# PowerSupply.net
KiCad netlist of a schematic drawn in Altium Designer
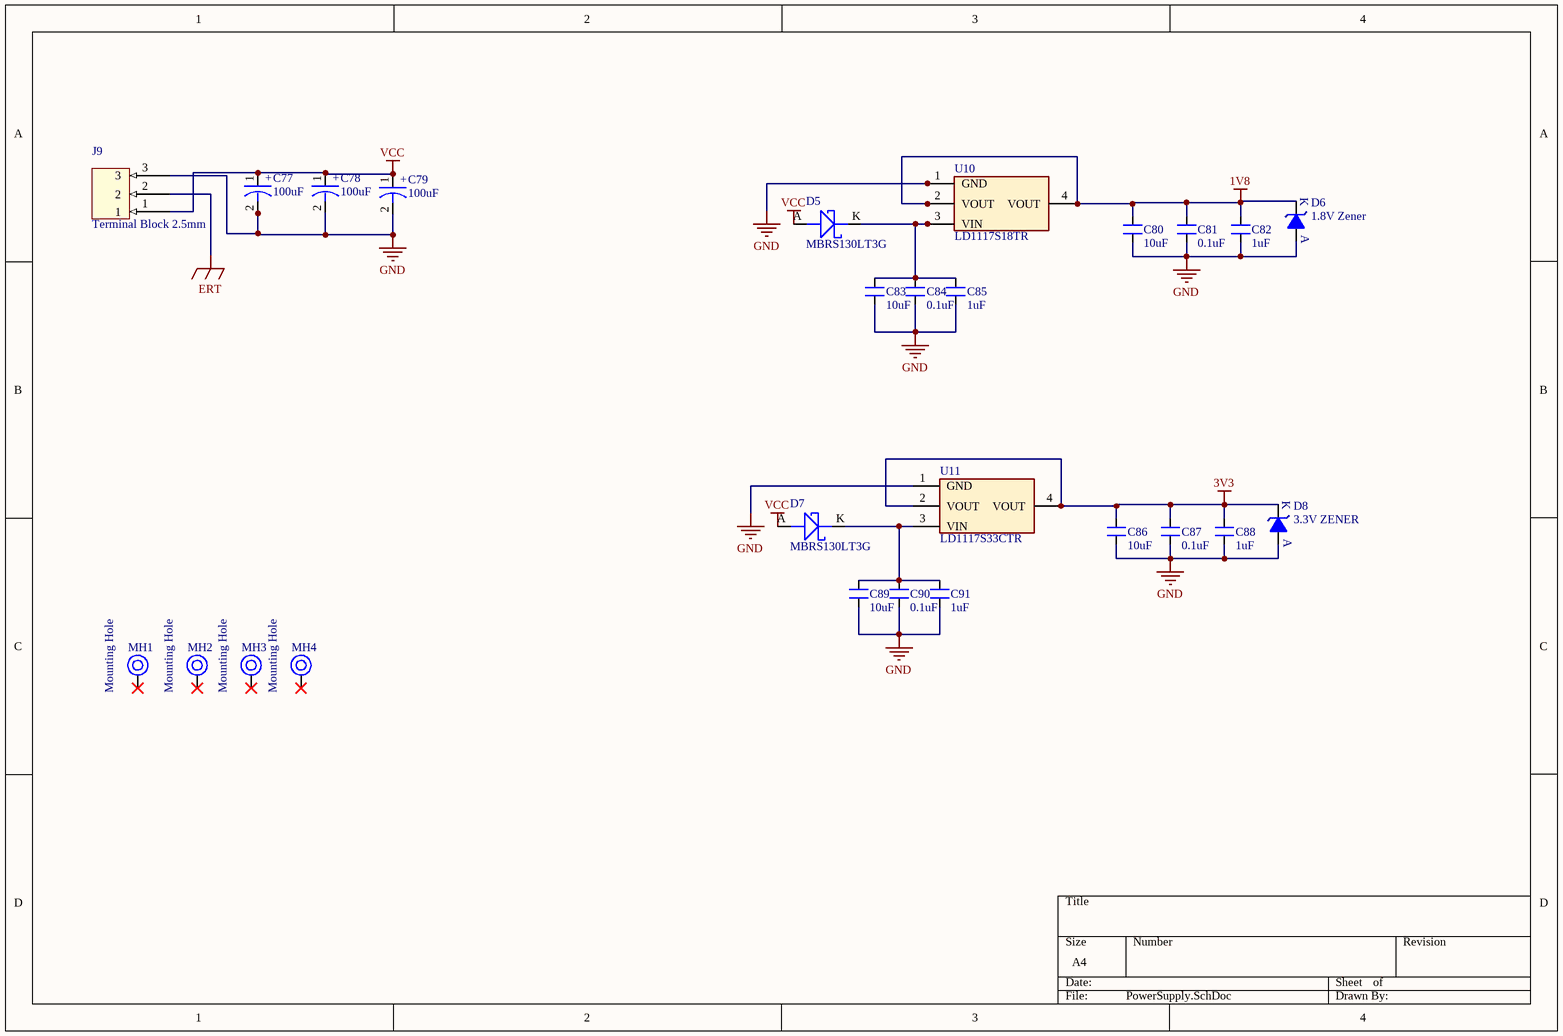
[diagram p0: PowerSupply.SchDoc]

(export (version "E")
  (design (tool "Eeschema 10.0.6"))
  (components
    (comp (ref "C77")
      (value "100uF")
      (footprint "ACAP_P236_D305_H303_RAD")
      (description "100µF 25V Aluminum Electrolytic Capacitors Radial, Can - SMD 1000 Hrs @ 105°C")
      (fields
        (field (name "MANUFACTURER") "Nichicon")
        (field (name "MANUFACTURER PART NUMBER") "UWT1E101MCL1GS")
      )
      (libsource (lib "ESTEEMPCBLIB") (part "CAP-P_100uF-25V-20%-RAD"))
    )
    (comp (ref "C78")
      (value "100uF")
      (footprint "ACAP_P236_D305_H303_RAD")
      (description "100µF 25V Aluminum Electrolytic Capacitors Radial, Can - SMD 1000 Hrs @ 105°C")
      (fields
        (field (name "MANUFACTURER") "Nichicon")
        (field (name "MANUFACTURER PART NUMBER") "UWT1E101MCL1GS")
      )
      (libsource (lib "ESTEEMPCBLIB") (part "CAP-P_100uF-25V-20%-RAD"))
    )
    (comp (ref "C79")
      (value "100uF")
      (footprint "ACAP_P236_D305_H303_RAD")
      (description "100µF 25V Aluminum Electrolytic Capacitors Radial, Can - SMD 1000 Hrs @ 105°C")
      (fields
        (field (name "MANUFACTURER") "Nichicon")
        (field (name "MANUFACTURER PART NUMBER") "UWT1E101MCL1GS")
      )
      (libsource (lib "ESTEEMPCBLIB") (part "CAP-P_100uF-25V-20%-RAD"))
    )
    (comp (ref "C80")
      (value "10uF")
      (footprint "CAP_1206")
      (description "10µF ±10% 50V Ceramic Capacitor X7R 1206 (3216 Metric)")
      (fields
        (field (name "MANUFACTURER") "KEMET")
        (field (name "MANUFACTURER PART NUMBER") "CL31B106KBHNNNE")
      )
      (libsource (lib "ESTEEMPCBLIB") (part "CAP_10uF-50V-10%-1206"))
    )
    (comp (ref "C81")
      (value "0.1uF")
      (footprint "CAP_0805")
      (description "0.1µF ±10% 50V Ceramic Capacitor X7R 0805 (2012 Metric)")
      (fields
        (field (name "MANUFACTURER") "Samsung")
        (field (name "MANUFACTURER PART NUMBER") "CL21B104KBCNNNC")
      )
      (libsource (lib "ESTEEMPCBLIB") (part "CAP_0.1uF-50V-10%-0805"))
    )
    (comp (ref "C82")
      (value "1uF")
      (footprint "CAP_0805")
      (description "1µF ±5% 50V Ceramic Capacitor X7R 0805 (2012 Metric)")
      (fields
        (field (name "MANUFACTURER") "Samsung")
        (field (name "MANUFACTURER PART NUMBER") "CC0805JKX7R9BB105")
      )
      (libsource (lib "ESTEEMPCBLIB") (part "CAP_1uF-50V-5%-0805"))
    )
    (comp (ref "C83")
      (value "10uF")
      (footprint "CAP_1206")
      (description "10µF ±10% 50V Ceramic Capacitor X7R 1206 (3216 Metric)")
      (fields
        (field (name "MANUFACTURER") "KEMET")
        (field (name "MANUFACTURER PART NUMBER") "CL31B106KBHNNNE")
      )
      (libsource (lib "ESTEEMPCBLIB") (part "CAP_10uF-50V-10%-1206"))
    )
    (comp (ref "C84")
      (value "0.1uF")
      (footprint "CAP_0805")
      (description "0.1µF ±10% 50V Ceramic Capacitor X7R 0805 (2012 Metric)")
      (fields
        (field (name "MANUFACTURER") "Samsung")
        (field (name "MANUFACTURER PART NUMBER") "CL21B104KBCNNNC")
      )
      (libsource (lib "ESTEEMPCBLIB") (part "CAP_0.1uF-50V-10%-0805"))
    )
    (comp (ref "C85")
      (value "1uF")
      (footprint "CAP_0805")
      (description "1µF ±5% 50V Ceramic Capacitor X7R 0805 (2012 Metric)")
      (fields
        (field (name "MANUFACTURER") "Samsung")
        (field (name "MANUFACTURER PART NUMBER") "CC0805JKX7R9BB105")
      )
      (libsource (lib "ESTEEMPCBLIB") (part "CAP_1uF-50V-5%-0805"))
    )
    (comp (ref "C86")
      (value "10uF")
      (footprint "CAP_1206")
      (description "10µF ±10% 50V Ceramic Capacitor X7R 1206 (3216 Metric)")
      (fields
        (field (name "MANUFACTURER") "KEMET")
        (field (name "MANUFACTURER PART NUMBER") "CL31B106KBHNNNE")
      )
      (libsource (lib "ESTEEMPCBLIB") (part "CAP_10uF-50V-10%-1206"))
    )
    (comp (ref "C87")
      (value "0.1uF")
      (footprint "CAP_0805")
      (description "0.1µF ±10% 50V Ceramic Capacitor X7R 0805 (2012 Metric)")
      (fields
        (field (name "MANUFACTURER") "Samsung")
        (field (name "MANUFACTURER PART NUMBER") "CL21B104KBCNNNC")
      )
      (libsource (lib "ESTEEMPCBLIB") (part "CAP_0.1uF-50V-10%-0805"))
    )
    (comp (ref "C88")
      (value "1uF")
      (footprint "CAP_0805")
      (description "1µF ±5% 50V Ceramic Capacitor X7R 0805 (2012 Metric)")
      (fields
        (field (name "MANUFACTURER") "Samsung")
        (field (name "MANUFACTURER PART NUMBER") "CC0805JKX7R9BB105")
      )
      (libsource (lib "ESTEEMPCBLIB") (part "CAP_1uF-50V-5%-0805"))
    )
    (comp (ref "C89")
      (value "10uF")
      (footprint "CAP_1206")
      (description "10µF ±10% 50V Ceramic Capacitor X7R 1206 (3216 Metric)")
      (fields
        (field (name "MANUFACTURER") "KEMET")
        (field (name "MANUFACTURER PART NUMBER") "CL31B106KBHNNNE")
      )
      (libsource (lib "ESTEEMPCBLIB") (part "CAP_10uF-50V-10%-1206"))
    )
    (comp (ref "C90")
      (value "0.1uF")
      (footprint "CAP_0805")
      (description "0.1µF ±10% 50V Ceramic Capacitor X7R 0805 (2012 Metric)")
      (fields
        (field (name "MANUFACTURER") "Samsung")
        (field (name "MANUFACTURER PART NUMBER") "CL21B104KBCNNNC")
      )
      (libsource (lib "ESTEEMPCBLIB") (part "CAP_0.1uF-50V-10%-0805"))
    )
    (comp (ref "C91")
      (value "1uF")
      (footprint "CAP_0805")
      (description "1µF ±5% 50V Ceramic Capacitor X7R 0805 (2012 Metric)")
      (fields
        (field (name "MANUFACTURER") "Samsung")
        (field (name "MANUFACTURER PART NUMBER") "CC0805JKX7R9BB105")
      )
      (libsource (lib "ESTEEMPCBLIB") (part "CAP_1uF-50V-5%-0805"))
    )
    (comp (ref "D5")
      (value "MBRS130LT3G")
      (footprint "DIO_SMB_DO-214AA")
      (description "Diode Schottky 30V 2A Surface Mount SMB")
      (fields (field (name "MANUFACTURER") "ON Semiconductor"))
      (libsource (lib "ESTEEMPCBLIB") (part "DIO-S_445mV-30V-2A-SMB"))
    )
    (comp (ref "D6")
      (value "1.8V Zener")
      (footprint "DIO_DO-213AB_SMD")
      (description "Zener Diode 1.8V 500mW ±5% Surface Mount DO-213AA")
      (libsource (lib "ESTEEMPCBLIB") (part "DIO-Z_1.8V-500mW-DO213AA"))
    )
    (comp (ref "D7")
      (value "MBRS130LT3G")
      (footprint "DIO_SMB_DO-214AA")
      (description "Diode Schottky 30V 2A Surface Mount SMB")
      (fields (field (name "MANUFACTURER") "ON Semiconductor"))
      (libsource (lib "ESTEEMPCBLIB") (part "DIO-S_445mV-30V-2A-SMB"))
    )
    (comp (ref "D8")
      (value "3.3V ZENER")
      (footprint "DIO_SOD80C")
      (description "Zener Diode 3.3V 500mW ±5% Surface Mount LLDS; MiniMelf")
      (fields
        (field (name "MANUFACTURER") "Vishay Semiconductors")
        (field (name "MANUFACTURER PART NUMBER") "BZV55-C3V3,135")
      )
      (libsource (lib "ESTEEMPCBLIB") (part "DIO-Z_3.3V-500mW-SOD-80"))
    )
    (comp (ref "J9")
      (value "Terminal Block 2.5mm")
      (footprint "CON3_100_TB_TH_ST")
      (description "3 Pins, 1 Row 2.54mm Pitch, straight Connector, male")
      (fields
        (field (name "MANUFACTURER PART NUMBER") "1725669")
        (field (name "MANUFACTURER") "Phoenix Contact")
      )
      (libsource (lib "ESTEEMPCBLIB") (part "CON-TB_3X1-100-ST-TH"))
    )
    (comp (ref "MH1")
      (value "Mounting Hole")
      (footprint "MOUNTING")
      (fields (field (name "MANUFACTURER PART NUMBER") "NA"))
      (libsource (lib "ESTEEMPCBLIB") (part "MH_3.5H_6D"))
    )
    (comp (ref "MH2")
      (value "Mounting Hole")
      (footprint "MOUNTING")
      (fields (field (name "MANUFACTURER PART NUMBER") "NA"))
      (libsource (lib "ESTEEMPCBLIB") (part "MH_3.5H_6D"))
    )
    (comp (ref "MH3")
      (value "Mounting Hole")
      (footprint "MOUNTING")
      (fields (field (name "MANUFACTURER PART NUMBER") "NA"))
      (libsource (lib "ESTEEMPCBLIB") (part "MH_3.5H_6D"))
    )
    (comp (ref "MH4")
      (value "Mounting Hole")
      (footprint "MOUNTING")
      (fields (field (name "MANUFACTURER PART NUMBER") "NA"))
      (libsource (lib "ESTEEMPCBLIB") (part "MH_3.5H_6D"))
    )
    (comp (ref "U10")
      (value "LD1117S18TR")
      (footprint "SOT223_3")
      (description "LDO Voltage Regulators 1.8V 0.8A Positive")
      (fields (field (name "MANUFACTURER") "STMicroelectronics"))
      (libsource (lib "ESTEEMPCBLIB") (part "REG_15V-1.8V-0.8A-1.4W-SOT223"))
    )
    (comp (ref "U11")
      (value "LD1117S33CTR")
      (footprint "SOT223_3")
      (description "Linear Voltage Regulator IC 1 Output 800mA SOT-223")
      (fields (field (name "MANUFACTURER") "STMicroelectronics"))
      (libsource (lib "ESTEEMPCBLIB") (part "REG_15V-3.3V-0.9A-12W-SOT223"))
    )
  )
  (nets
    (net (code "1") (name "1V8") (class "Default")
      (node (ref "C80") (pin "2") (pinfunction "2_2") (pintype "passive"))
      (node (ref "C81") (pin "2") (pinfunction "2_2") (pintype "passive"))
      (node (ref "C82") (pin "2") (pinfunction "2_2") (pintype "passive"))
      (node (ref "D6") (pin "K") (pinfunction "K_K") (pintype "passive"))
      (node (ref "U10") (pin "2") (pinfunction "VOUT_2") (pintype "passive"))
      (node (ref "U10") (pin "4") (pinfunction "VOUT_4") (pintype "passive"))
    )
    (net (code "2") (name "3V3") (class "Default")
      (node (ref "C86") (pin "2") (pinfunction "2_2") (pintype "passive"))
      (node (ref "C87") (pin "2") (pinfunction "2_2") (pintype "passive"))
      (node (ref "C88") (pin "2") (pinfunction "2_2") (pintype "passive"))
      (node (ref "D8") (pin "K") (pinfunction "K_K") (pintype "passive"))
      (node (ref "U11") (pin "2") (pinfunction "VOUT_2") (pintype "passive"))
      (node (ref "U11") (pin "4") (pinfunction "VOUT_4") (pintype "passive"))
    )
    (net (code "3") (name "ERT") (class "Default")
      (node (ref "J9") (pin "2") (pinfunction "2_2") (pintype "input"))
    )
    (net (code "4") (name "GND") (class "Default")
      (node (ref "C77") (pin "2") (pinfunction "2_2") (pintype "passive"))
      (node (ref "C78") (pin "2") (pinfunction "2_2") (pintype "passive"))
      (node (ref "C79") (pin "2") (pinfunction "2_2") (pintype "passive"))
      (node (ref "C80") (pin "1") (pinfunction "1_1") (pintype "passive"))
      (node (ref "C81") (pin "1") (pinfunction "1_1") (pintype "passive"))
      (node (ref "C82") (pin "1") (pinfunction "1_1") (pintype "passive"))
      (node (ref "C83") (pin "1") (pinfunction "1_1") (pintype "passive"))
      (node (ref "C84") (pin "1") (pinfunction "1_1") (pintype "passive"))
      (node (ref "C85") (pin "1") (pinfunction "1_1") (pintype "passive"))
      (node (ref "C86") (pin "1") (pinfunction "1_1") (pintype "passive"))
      (node (ref "C87") (pin "1") (pinfunction "1_1") (pintype "passive"))
      (node (ref "C88") (pin "1") (pinfunction "1_1") (pintype "passive"))
      (node (ref "C89") (pin "1") (pinfunction "1_1") (pintype "passive"))
      (node (ref "C90") (pin "1") (pinfunction "1_1") (pintype "passive"))
      (node (ref "C91") (pin "1") (pinfunction "1_1") (pintype "passive"))
      (node (ref "D6") (pin "A") (pinfunction "A_A") (pintype "passive"))
      (node (ref "D8") (pin "A") (pinfunction "A_A") (pintype "passive"))
      (node (ref "J9") (pin "3") (pinfunction "3_3") (pintype "input"))
      (node (ref "U10") (pin "1") (pinfunction "GND_1") (pintype "passive"))
      (node (ref "U11") (pin "1") (pinfunction "GND_1") (pintype "passive"))
    )
    (net (code "5") (name "Net-(U10-VIN)") (class "Default")
      (node (ref "C83") (pin "2") (pinfunction "2_2") (pintype "passive"))
      (node (ref "C84") (pin "2") (pinfunction "2_2") (pintype "passive"))
      (node (ref "C85") (pin "2") (pinfunction "2_2") (pintype "passive"))
      (node (ref "D5") (pin "K") (pinfunction "K_K") (pintype "passive"))
      (node (ref "U10") (pin "3") (pinfunction "VIN_3") (pintype "passive"))
    )
    (net (code "6") (name "Net-(U11-VIN)") (class "Default")
      (node (ref "C89") (pin "2") (pinfunction "2_2") (pintype "passive"))
      (node (ref "C90") (pin "2") (pinfunction "2_2") (pintype "passive"))
      (node (ref "C91") (pin "2") (pinfunction "2_2") (pintype "passive"))
      (node (ref "D7") (pin "K") (pinfunction "K_K") (pintype "passive"))
      (node (ref "U11") (pin "3") (pinfunction "VIN_3") (pintype "passive"))
    )
    (net (code "7") (name "VCC") (class "Default")
      (node (ref "C77") (pin "1") (pinfunction "1_1") (pintype "passive"))
      (node (ref "C78") (pin "1") (pinfunction "1_1") (pintype "passive"))
      (node (ref "C79") (pin "1") (pinfunction "1_1") (pintype "passive"))
      (node (ref "D5") (pin "A") (pinfunction "A_A") (pintype "passive"))
      (node (ref "D7") (pin "A") (pinfunction "A_A") (pintype "passive"))
      (node (ref "J9") (pin "1") (pinfunction "1_1") (pintype "input"))
    )
    (net (code "8") (name "unconnected-(MH1-Pad1)") (class "Default")
      (node (ref "MH1") (pin "1") (pinfunction "1_1") (pintype "passive+no_connect"))
    )
    (net (code "9") (name "unconnected-(MH2-Pad1)") (class "Default")
      (node (ref "MH2") (pin "1") (pinfunction "1_1") (pintype "passive+no_connect"))
    )
    (net (code "10") (name "unconnected-(MH3-Pad1)") (class "Default")
      (node (ref "MH3") (pin "1") (pinfunction "1_1") (pintype "passive+no_connect"))
    )
    (net (code "11") (name "unconnected-(MH4-Pad1)") (class "Default")
      (node (ref "MH4") (pin "1") (pinfunction "1_1") (pintype "passive+no_connect"))
    )
  )
)
